# SUPPLY_v40.net
KiCad netlist of a schematic drawn in Altium Designer
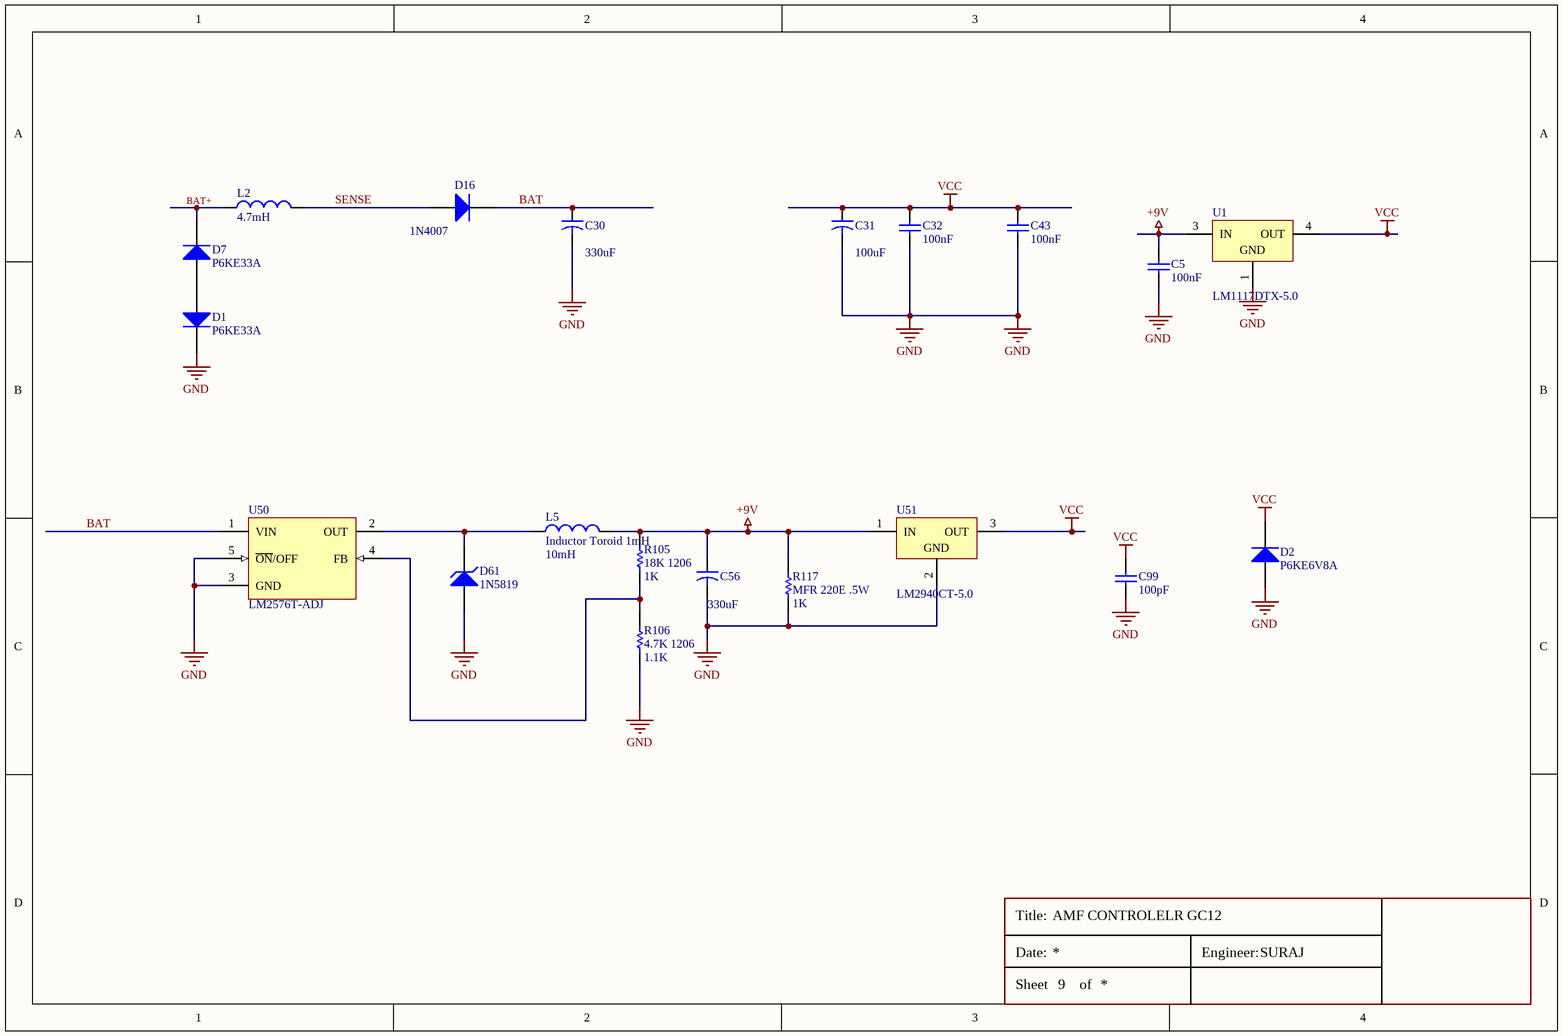
[diagram p0: SUPPLY_v40.SchDoc]

(export (version "E")
  (design (tool "Eeschema 10.0.6"))
  (components
    (comp (ref "C5")
      (value "100nF")
      (footprint "C1206")
      (description "Capacitor")
      (fields (field (name "Comment") ".1uF 1206") (field (name "PUBLISHER") "Altium Limited"))
      (libsource (lib "Miscellaneous Devices") (part "Cap"))
    )
    (comp (ref "C30")
      (value "330uF")
      (footprint "Cap_.2-2")
      (description "Capacitor")
      (fields (field (name "Comment") "Cap 1000uF/35V") (field (name "PUBLISHER") "Altium Limited"))
      (libsource (lib "Miscellaneous Devices") (part "Cap2"))
    )
    (comp (ref "C31")
      (value "100uF")
      (footprint "Cap_.2-2")
      (description "Capacitor")
      (fields (field (name "Comment") "Cap 470uF/16V") (field (name "PUBLISHER") "Altium Limited"))
      (libsource (lib "Miscellaneous Devices") (part "Cap2"))
    )
    (comp (ref "C32")
      (value "100nF")
      (footprint "C1206")
      (description "Capacitor")
      (fields (field (name "Comment") ".1uF 1206") (field (name "PUBLISHER") "Altium Limited"))
      (libsource (lib "Miscellaneous Devices") (part "Cap"))
    )
    (comp (ref "C43")
      (value "100nF")
      (footprint "C1206")
      (description "Capacitor")
      (fields (field (name "Comment") "1uF 1206") (field (name "PUBLISHER") "Altium Limited"))
      (libsource (lib "Miscellaneous Devices") (part "Cap"))
    )
    (comp (ref "C56")
      (value "330uF")
      (footprint "Cap_.3")
      (description "Capacitor")
      (fields
        (field (name "Comment") "Cap Electrolitic 3300uF/16V")
        (field (name "PUBLISHER") "Altium Limited")
      )
      (libsource (lib "Miscellaneous Devices") (part "Cap2"))
    )
    (comp (ref "C99")
      (value "100pF")
      (footprint "C1206")
      (description "Capacitor")
      (fields (field (name "Comment") ".1uF 1206") (field (name "PUBLISHER") "Altium Limited"))
      (libsource (lib "Miscellaneous Devices") (part "Cap"))
    )
    (comp (ref "D1")
      (value "P6KE33A")
      (footprint "DIODE1A")
      (description "3 Amp Medium Power Silicon Rectifier Diode")
      (fields (field (name "PUBLISHER") "Altium Limited"))
      (libsource (lib "Miscellaneous Devices") (part "Diode 1N5408"))
    )
    (comp (ref "D2")
      (value "P6KE6V8A")
      (footprint "DIODE1A")
      (description "3 Amp Medium Power Silicon Rectifier Diode")
      (fields (field (name "PUBLISHER") "Altium Limited"))
      (libsource (lib "Miscellaneous Devices") (part "Diode 1N5408"))
    )
    (comp (ref "D7")
      (value "P6KE33A")
      (footprint "DIODE1A")
      (description "3 Amp Medium Power Silicon Rectifier Diode")
      (fields (field (name "PUBLISHER") "Altium Limited"))
      (libsource (lib "Miscellaneous Devices") (part "Diode 1N5408"))
    )
    (comp (ref "D16")
      (value "1N4007")
      (footprint "DIODE1A")
      (description "3 Amp Medium Power Silicon Rectifier Diode")
      (fields (field (name "PUBLISHER") "Altium Limited"))
      (libsource (lib "Miscellaneous Devices") (part "Diode 1N5408"))
    )
    (comp (ref "D61")
      (value "1N5819")
      (footprint "DIODE1A")
      (description "Silicon Zener Diode (0.3 to 0.5W)")
      (fields (field (name "PUBLISHER") "Altium Limited"))
      (libsource (lib "Vishay Telefunken Discrete Diode") (part "1N5221B"))
    )
    (comp (ref "L2")
      (value "4.7mH")
      (footprint "INDUCTOR")
      (description "Inductor")
      (fields (field (name "Comment") "Inductor 47uH") (field (name "PUBLISHER") "Altium Limited"))
      (libsource (lib "Miscellaneous Devices") (part "Inductor"))
    )
    (comp (ref "L5")
      (value "Inductor Toroid 1mH")
      (footprint "INDUCTORTOROID")
      (description "Inductor")
      (fields (field (name "ALTIUM_VALUE") "10mH") (field (name "PUBLISHER") "Altium Limited"))
      (libsource (lib "Miscellaneous Devices") (part "Inductor"))
    )
    (comp (ref "R105")
      (value "18K 1206")
      (footprint "R1206")
      (description "Semiconductor Resistor")
      (fields (field (name "ALTIUM_VALUE") "1K") (field (name "PUBLISHER") "Altium Limited"))
      (libsource (lib "PCB_Project1") (part "Res SMT"))
    )
    (comp (ref "R106")
      (value "4.7K 1206")
      (footprint "R1206")
      (description "Semiconductor Resistor")
      (fields (field (name "ALTIUM_VALUE") "1.1K") (field (name "PUBLISHER") "Altium Limited"))
      (libsource (lib "PCB_Project1") (part "Res SMT"))
    )
    (comp (ref "R117")
      (value "MFR 220E .5W")
      (footprint "AXIAL-0.5")
      (description "Semiconductor Resistor")
      (fields (field (name "ALTIUM_VALUE") "1K") (field (name "PUBLISHER") "Altium Limited"))
      (libsource (lib "Miscellaneous Devices") (part "Res Semi"))
    )
    (comp (ref "U1")
      (value "LM1117DTX-5.0")
      (footprint "TD03B_N")
      (description "800mA Low-Dropout Linear Regulator, 3-pin TO-252")
      (fields
        (field (name "MANUFACTURER") "National Semiconductor")
        (field (name "PUBLISHER") "Altium Limited")
      )
      (libsource (lib "NSC LDO") (part "LM1117DTX-5.0"))
    )
    (comp (ref "U50")
      (value "LM2576T-ADJ")
      (footprint "T05D")
      (description "SIMPLE SWITCHER® 3A Step-Down Voltage Regulator, 5-pin TO-220")
      (fields
        (field (name "MANUFACTURER") "National Semiconductor")
        (field (name "PUBLISHER") "Altium Limited")
      )
      (libsource (lib "NSC Switcher") (part "LM2576T-ADJ"))
    )
    (comp (ref "U51")
      (value "LM2940CT-5.0")
      (footprint "T03B")
      (description "1A Low Dropout Regulator, 3-pin TO-220")
      (fields
        (field (name "MANUFACTURER") "National Semiconductor")
        (field (name "PUBLISHER") "Altium Limited")
      )
      (libsource (lib "NSC LDO") (part "LM2940CT-5.0"))
    )
  )
  (nets
    (net (code "1") (name "+9V") (class "Default")
      (node (ref "C5") (pin "2") (pinfunction "2_2") (pintype "passive"))
      (node (ref "C56") (pin "1") (pinfunction "1_1") (pintype "passive"))
      (node (ref "L5") (pin "2") (pinfunction "2_2") (pintype "passive"))
      (node (ref "R105") (pin "2") (pinfunction "2_2") (pintype "passive"))
      (node (ref "R117") (pin "2") (pinfunction "2_2") (pintype "passive"))
      (node (ref "U1") (pin "3") (pinfunction "IN_3") (pintype "power_in"))
      (node (ref "U51") (pin "1") (pinfunction "IN_1") (pintype "power_in"))
    )
    (net (code "2") (name "/BAT") (class "Default")
      (node (ref "C30") (pin "1") (pinfunction "1_1") (pintype "passive"))
      (node (ref "D16") (pin "2") (pinfunction "K_2") (pintype "passive"))
      (node (ref "U50") (pin "1") (pinfunction "VIN_1") (pintype "power_in"))
    )
    (net (code "3") (name "/BAT+") (class "Default")
      (node (ref "D7") (pin "2") (pinfunction "K_2") (pintype "passive"))
      (node (ref "L2") (pin "1") (pinfunction "1_1") (pintype "passive"))
    )
    (net (code "4") (name "/SENSE") (class "Default")
      (node (ref "D16") (pin "1") (pinfunction "A_1") (pintype "passive"))
      (node (ref "L2") (pin "2") (pinfunction "2_2") (pintype "passive"))
    )
    (net (code "5") (name "GND") (class "Default")
      (node (ref "C30") (pin "2") (pinfunction "2_2") (pintype "passive"))
      (node (ref "C31") (pin "2") (pinfunction "2_2") (pintype "passive"))
      (node (ref "C32") (pin "1") (pinfunction "1_1") (pintype "passive"))
      (node (ref "C43") (pin "1") (pinfunction "1_1") (pintype "passive"))
      (node (ref "C5") (pin "1") (pinfunction "1_1") (pintype "passive"))
      (node (ref "C56") (pin "2") (pinfunction "2_2") (pintype "passive"))
      (node (ref "C99") (pin "1") (pinfunction "1_1") (pintype "passive"))
      (node (ref "D1") (pin "2") (pinfunction "K_2") (pintype "passive"))
      (node (ref "D2") (pin "1") (pinfunction "A_1") (pintype "passive"))
      (node (ref "D61") (pin "1") (pinfunction "A_1") (pintype "passive"))
      (node (ref "R106") (pin "1") (pinfunction "1_1") (pintype "passive"))
      (node (ref "R117") (pin "1") (pinfunction "1_1") (pintype "passive"))
      (node (ref "U1") (pin "1") (pinfunction "GND_1") (pintype "power_in"))
      (node (ref "U50") (pin "3") (pinfunction "GND_3") (pintype "power_in"))
      (node (ref "U50") (pin "5") (pinfunction "~{ON}/OFF_5") (pintype "input"))
      (node (ref "U51") (pin "2") (pinfunction "GND_2") (pintype "power_in"))
    )
    (net (code "6") (name "Net-(D1-A)") (class "Default")
      (node (ref "D1") (pin "1") (pinfunction "A_1") (pintype "passive"))
      (node (ref "D7") (pin "1") (pinfunction "A_1") (pintype "passive"))
    )
    (net (code "7") (name "Net-(D61-K)") (class "Default")
      (node (ref "D61") (pin "2") (pinfunction "K_2") (pintype "passive"))
      (node (ref "L5") (pin "1") (pinfunction "1_1") (pintype "passive"))
      (node (ref "U50") (pin "2") (pinfunction "OUT_2") (pintype "power_in"))
    )
    (net (code "8") (name "Net-(U50-FB)") (class "Default")
      (node (ref "R105") (pin "1") (pinfunction "1_1") (pintype "passive"))
      (node (ref "R106") (pin "2") (pinfunction "2_2") (pintype "passive"))
      (node (ref "U50") (pin "4") (pinfunction "FB_4") (pintype "input"))
    )
    (net (code "9") (name "VCC") (class "Default")
      (node (ref "C31") (pin "1") (pinfunction "1_1") (pintype "passive"))
      (node (ref "C32") (pin "2") (pinfunction "2_2") (pintype "passive"))
      (node (ref "C43") (pin "2") (pinfunction "2_2") (pintype "passive"))
      (node (ref "C99") (pin "2") (pinfunction "2_2") (pintype "passive"))
      (node (ref "D2") (pin "2") (pinfunction "K_2") (pintype "passive"))
      (node (ref "U1") (pin "4") (pinfunction "OUT_4") (pintype "power_in"))
      (node (ref "U51") (pin "3") (pinfunction "OUT_3") (pintype "power_in"))
    )
  )
)
